# LightTable_Borders_CurrentMirrorSinglePi.net
KiCad netlist of a schematic drawn in EAGLE
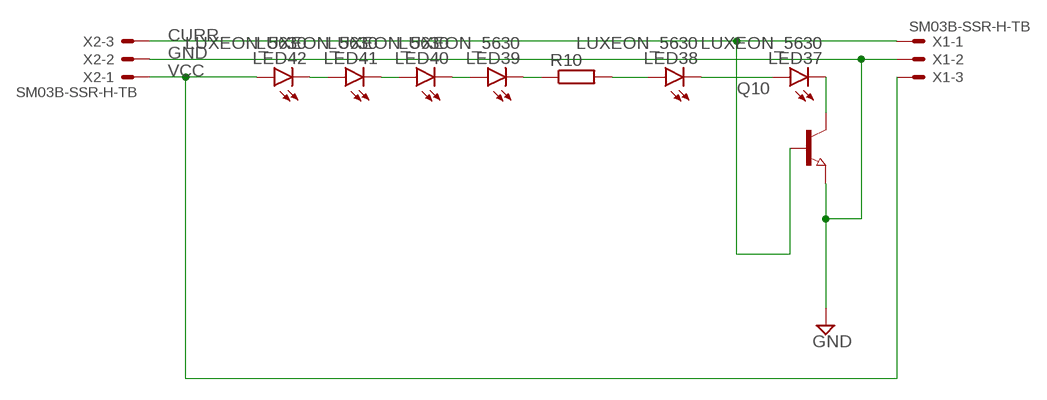
[diagram p0: schematic, sheet 1]

(export (version "E")
  (design (tool "Eeschema 10.0.6"))
  (components
    (comp (ref "LED37")
      (value "LUXEON_5630")
      (footprint "eagle-import:LUXEON_5630")
      (libsource (lib "eagle-import") (part "LUXEON_5630"))
    )
    (comp (ref "LED38")
      (value "LUXEON_5630")
      (footprint "eagle-import:LUXEON_5630")
      (libsource (lib "eagle-import") (part "LUXEON_5630"))
    )
    (comp (ref "LED39")
      (value "LUXEON_5630")
      (footprint "eagle-import:LUXEON_5630")
      (libsource (lib "eagle-import") (part "LUXEON_5630"))
    )
    (comp (ref "LED40")
      (value "LUXEON_5630")
      (footprint "eagle-import:LUXEON_5630")
      (libsource (lib "eagle-import") (part "LUXEON_5630"))
    )
    (comp (ref "LED41")
      (value "LUXEON_5630")
      (footprint "eagle-import:LUXEON_5630")
      (libsource (lib "eagle-import") (part "LUXEON_5630"))
    )
    (comp (ref "LED42")
      (value "LUXEON_5630")
      (footprint "eagle-import:LUXEON_5630")
      (libsource (lib "eagle-import") (part "LUXEON_5630"))
    )
    (comp (ref "Q10")
      (value "NPN-TRANSISTOR_SOT23")
      (footprint "eagle-import:SOT23")
      (libsource (lib "eagle-import") (part "NPN-TRANSISTOR_SOT23"))
    )
    (comp (ref "R10")
      (value "R-EU_R0805")
      (footprint "eagle-import:R0805")
      (libsource (lib "eagle-import") (part "R-EU_R0805"))
    )
    (comp (ref "X1")
      (value "SM03B-SSR-H-TB")
      (footprint "eagle-import:SM03B-SSR-H-TB")
      (libsource (lib "eagle-import") (part "SM03B-SSR-H-TB"))
    )
    (comp (ref "X2")
      (value "SM03B-SSR-H-TB")
      (footprint "eagle-import:SM03B-SSR-H-TB")
      (libsource (lib "eagle-import") (part "SM03B-SSR-H-TB"))
    )
  )
  (nets
    (net (code "1") (name "/CURR") (class "Default")
      (node (ref "Q10") (pin "1") (pinfunction "B_1") (pintype "passive"))
      (node (ref "X1") (pin "1") (pinfunction "S_1") (pintype "passive"))
      (node (ref "X2") (pin "3") (pinfunction "S_3") (pintype "passive"))
    )
    (net (code "2") (name "/VCC") (class "Default")
      (node (ref "LED42") (pin "2") (pinfunction "A_2") (pintype "passive"))
      (node (ref "X1") (pin "3") (pinfunction "S_3") (pintype "passive"))
      (node (ref "X2") (pin "1") (pinfunction "S_1") (pintype "passive"))
    )
    (net (code "3") (name "GND") (class "Default")
      (node (ref "Q10") (pin "2") (pinfunction "E_2") (pintype "passive"))
      (node (ref "X1") (pin "2") (pinfunction "S_2") (pintype "passive"))
      (node (ref "X2") (pin "2") (pinfunction "S_2") (pintype "passive"))
    )
    (net (code "4") (name "Net-(LED37-A)") (class "Default")
      (node (ref "LED37") (pin "2") (pinfunction "A_2") (pintype "passive"))
      (node (ref "LED38") (pin "1@1") (pinfunction "C_1@1") (pintype "passive"))
      (node (ref "LED38") (pin "1@2") (pinfunction "C_1@2") (pintype "passive"))
    )
    (net (code "5") (name "Net-(LED38-A)") (class "Default")
      (node (ref "LED38") (pin "2") (pinfunction "A_2") (pintype "passive"))
      (node (ref "R10") (pin "2") (pinfunction "2_2") (pintype "passive"))
    )
    (net (code "6") (name "Net-(LED39-A)") (class "Default")
      (node (ref "LED39") (pin "2") (pinfunction "A_2") (pintype "passive"))
      (node (ref "LED40") (pin "1@1") (pinfunction "C_1@1") (pintype "passive"))
      (node (ref "LED40") (pin "1@2") (pinfunction "C_1@2") (pintype "passive"))
    )
    (net (code "7") (name "Net-(LED39-C-Pad1@1)") (class "Default")
      (node (ref "LED39") (pin "1@1") (pinfunction "C_1@1") (pintype "passive"))
      (node (ref "LED39") (pin "1@2") (pinfunction "C_1@2") (pintype "passive"))
      (node (ref "R10") (pin "1") (pinfunction "1_1") (pintype "passive"))
    )
    (net (code "8") (name "Net-(LED40-A)") (class "Default")
      (node (ref "LED40") (pin "2") (pinfunction "A_2") (pintype "passive"))
      (node (ref "LED41") (pin "1@1") (pinfunction "C_1@1") (pintype "passive"))
      (node (ref "LED41") (pin "1@2") (pinfunction "C_1@2") (pintype "passive"))
    )
    (net (code "9") (name "Net-(LED41-A)") (class "Default")
      (node (ref "LED41") (pin "2") (pinfunction "A_2") (pintype "passive"))
      (node (ref "LED42") (pin "1@1") (pinfunction "C_1@1") (pintype "passive"))
      (node (ref "LED42") (pin "1@2") (pinfunction "C_1@2") (pintype "passive"))
    )
    (net (code "10") (name "Net-(Q10-C)") (class "Default")
      (node (ref "LED37") (pin "1@1") (pinfunction "C_1@1") (pintype "passive"))
      (node (ref "LED37") (pin "1@2") (pinfunction "C_1@2") (pintype "passive"))
      (node (ref "Q10") (pin "3") (pinfunction "C_3") (pintype "passive"))
    )
  )
)
